# main.net
KiCad netlist of a schematic drawn in Altium Designer
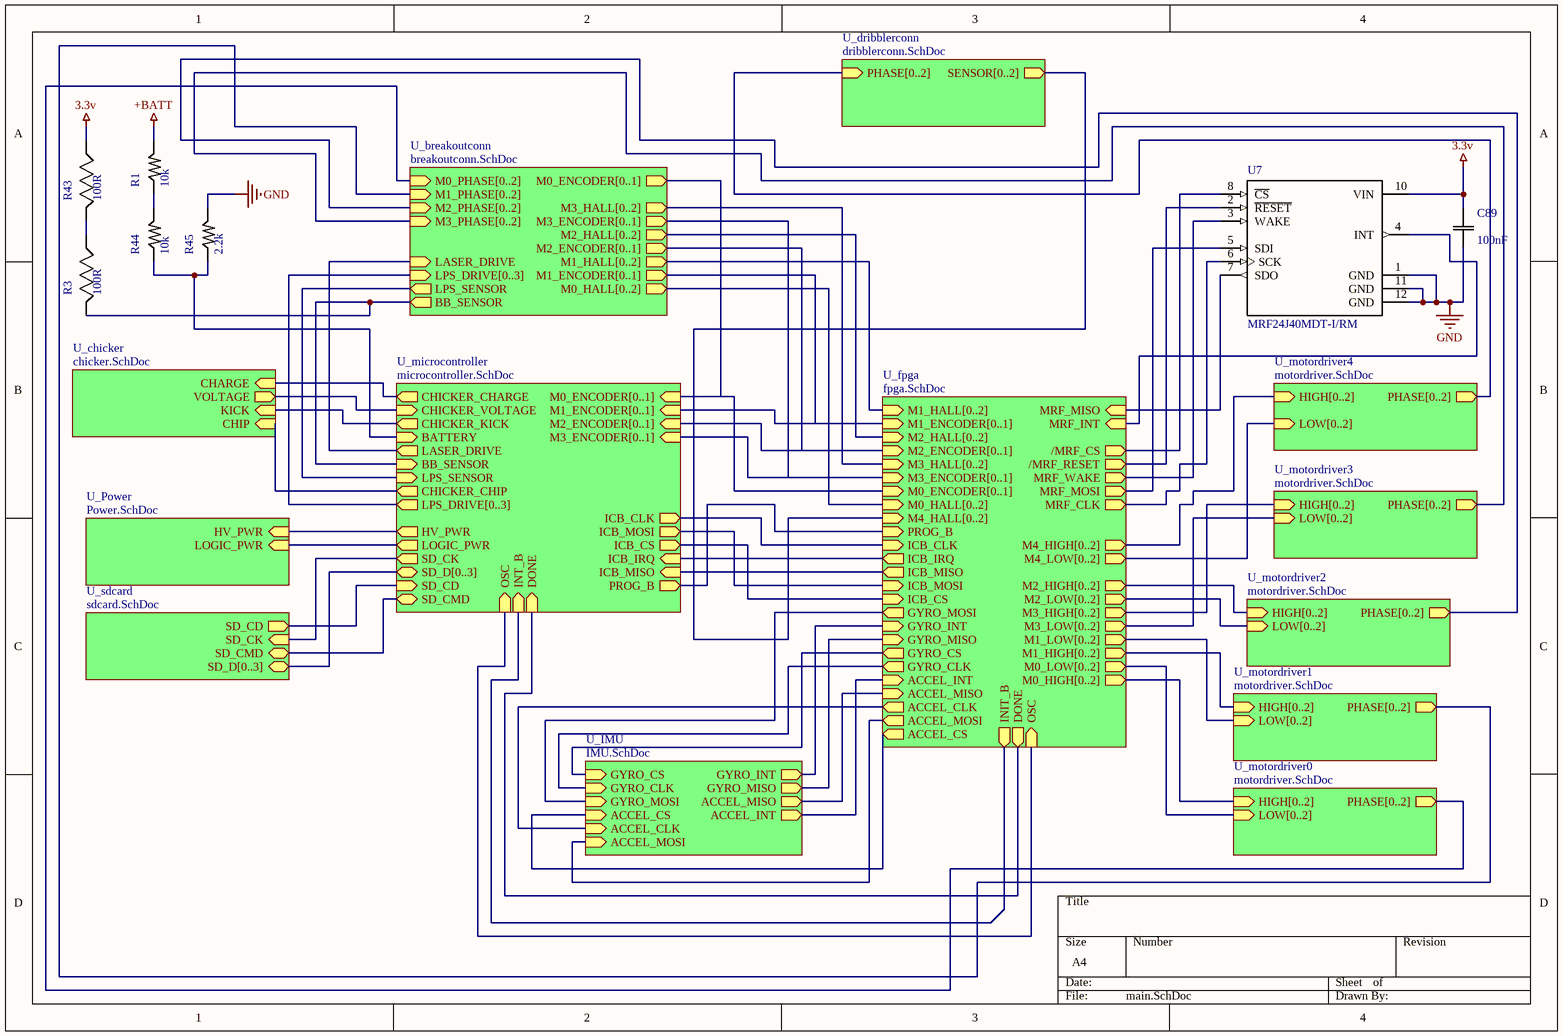
[diagram p0: main.SchDoc]

(export (version "E")
  (design (tool "Eeschema 10.0.6"))
  (components
    (comp (ref "C89")
      (value "100nF")
      (footprint "CAPC2013X110N")
      (description "Capacitor; Ceramic; Cap; .100UF ; Tol+-10%; SMD; Vol-Rtg 50V; X7R, Tape/Reel")
      (fields (field (name "MP") "C0805C104K5RACTU") (field (name "MF") "Kemet"))
      (libsource (lib "100nF-C0805C104K5RACTU") (part "C0805C104K5RACTU"))
    )
    (comp (ref "R1")
      (value "10k")
      (footprint "RESC2012X60")
      (description "RES SMD 10K OHM 1% 1/8W 0805")
      (fields (field (name "MP") "RC0805FR-0710KL") (field (name "MF") "Yageo"))
      (libsource (lib "10KOhm") (part "RC0805FR-0710KL"))
    )
    (comp (ref "R3")
      (value "100R")
      (footprint "RESC2012X60")
      (description "RES SMD 100 OHM 1% 1/8W 0805")
      (fields (field (name "MP") "RC0805FR-07100RL") (field (name "MF") "Yageo"))
      (libsource (lib "RC0805FR-07100RL") (part "RC0805FR-07100RL"))
    )
    (comp (ref "R43")
      (value "100R")
      (footprint "RESC2012X60")
      (description "RES SMD 100 OHM 1% 1/8W 0805")
      (fields (field (name "MP") "RC0805FR-07100RL") (field (name "MF") "Yageo"))
      (libsource (lib "RC0805FR-07100RL") (part "RC0805FR-07100RL"))
    )
    (comp (ref "R44")
      (value "10k")
      (footprint "RESC2012X60")
      (description "RES SMD 10K OHM 1% 1/8W 0805")
      (fields (field (name "MP") "RC0805FR-0710KL") (field (name "MF") "Yageo"))
      (libsource (lib "10KOhm") (part "RC0805FR-0710KL"))
    )
    (comp (ref "R45")
      (value "2.2k")
      (footprint "RESC2012X60")
      (description "RES SMD 10K OHM 1% 1/8W 0805")
      (fields (field (name "MP") "RC0805FR-0710KL") (field (name "MF") "Yageo"))
      (libsource (lib "10KOhm") (part "RC0805FR-0710KL"))
    )
    (comp (ref "U7")
      (value "MRF24J40MDT-I/RM")
      (footprint "XCVR_MRF24J40MDT-I/RM")
      (description "2.4 GHz IEEE 802.15.4 Certified Transceiver Module (+20 dBm), 12 MODULE Varies T/R")
      (fields (field (name "MF") "Microchip"))
      (libsource (lib "MRF24J40MDT-I_RM") (part "MRF24J40MDT-I/RM"))
    )
  )
  (nets
    (net (code "1") (name "+BATT") (class "Default")
      (node (ref "R1") (pin "2") (pinfunction "2_2") (pintype "passive"))
    )
    (net (code "7") (name "/BATTERY") (class "Default")
      (node (ref "R44") (pin "1") (pinfunction "1_1") (pintype "passive"))
      (node (ref "R45") (pin "1") (pinfunction "1_1") (pintype "passive"))
    )
    (net (code "8") (name "/BB_SENSOR") (class "Default")
      (node (ref "R3") (pin "1") (pinfunction "1_1") (pintype "passive"))
    )
    (net (code "47") (name "/MRF_CLK") (class "Default")
      (node (ref "U7") (pin "6") (pinfunction "SCK_6") (pintype "input"))
    )
    (net (code "48") (name "/MRF_INT") (class "Default")
      (node (ref "U7") (pin "4") (pinfunction "INT_4") (pintype "output"))
    )
    (net (code "49") (name "/MRF_MISO") (class "Default")
      (node (ref "U7") (pin "7") (pinfunction "SDO_7") (pintype "output"))
    )
    (net (code "50") (name "/MRF_MOSI") (class "Default")
      (node (ref "U7") (pin "5") (pinfunction "SDI_5") (pintype "input"))
    )
    (net (code "51") (name "/MRF_WAKE") (class "Default")
      (node (ref "U7") (pin "3") (pinfunction "WAKE_3") (pintype "input"))
    )
    (net (code "65") (name "/{slash}MRF_CS") (class "Default")
      (node (ref "U7") (pin "8") (pinfunction "~{CS}_8") (pintype "input"))
    )
    (net (code "66") (name "/{slash}MRF_RESET") (class "Default")
      (node (ref "U7") (pin "2") (pinfunction "~{RESET}_2") (pintype "input"))
    )
    (net (code "67") (name "3.3v") (class "Default")
      (node (ref "C89") (pin "2") (pinfunction "C2_2") (pintype "passive"))
      (node (ref "R43") (pin "2") (pinfunction "2_2") (pintype "passive"))
      (node (ref "U7") (pin "10") (pinfunction "VIN_10") (pintype "power_in"))
    )
    (net (code "68") (name "GND") (class "Default")
      (node (ref "C89") (pin "1") (pinfunction "C1_1") (pintype "passive"))
      (node (ref "R45") (pin "2") (pinfunction "2_2") (pintype "passive"))
      (node (ref "U7") (pin "1") (pinfunction "GND_1") (pintype "power_in"))
      (node (ref "U7") (pin "11") (pinfunction "GND_11") (pintype "power_in"))
      (node (ref "U7") (pin "12") (pinfunction "GND_12") (pintype "power_in"))
    )
    (net (code "69") (name "Net-(R1-Pad1)") (class "Default")
      (node (ref "R1") (pin "1") (pinfunction "1_1") (pintype "passive"))
      (node (ref "R44") (pin "2") (pinfunction "2_2") (pintype "passive"))
    )
    (net (code "70") (name "Net-(R3-Pad2)") (class "Default")
      (node (ref "R3") (pin "2") (pinfunction "2_2") (pintype "passive"))
      (node (ref "R43") (pin "1") (pinfunction "1_1") (pintype "passive"))
    )
  )
)
